# EPS_Distribution_RLCL-FPF.net
KiCad netlist of a schematic drawn in Altium Designer
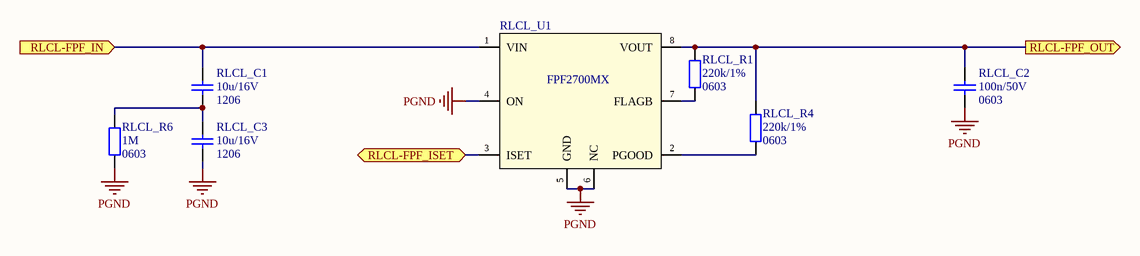
[diagram p0: EPS_Distribution_RLCL-FPF.SchDoc]

(export (version "E")
  (design (tool "Eeschema 10.0.6"))
  (components
    (comp (ref "RLCL_C1")
      (value "10u/16V")
      (footprint "SMD_Capacitor_1206")
      (description "Ceramic Cap Kemet COTS 10u/16V X7R 1206")
      (fields
        (field (name "MANUFACTURERPARTNUMBER") "C1206T106K4RACTU")
        (field (name "MANUFACTURER") "Kemet")
        (field (name "PACKGE") "1206")
      )
      (libsource (lib "capacitors") (part "Cer_C1206T106K4RACTU"))
    )
    (comp (ref "RLCL_C2")
      (value "100n/50V")
      (footprint "SMD_Capacitor_0603")
      (description "Ceramic Cap Kemet COTS 100n/50V X7R 0603")
      (fields
        (field (name "MANUFACTURER") "Kemet")
        (field (name "MANUFACTURERPARTNUMBER") "C0603T104K5RALTU")
        (field (name "PACKAGE") "0603")
      )
      (libsource (lib "capacitors") (part "Cer_C0603T104K5RALTU"))
    )
    (comp (ref "RLCL_C3")
      (value "10u/16V")
      (footprint "SMD_Capacitor_1206")
      (description "Ceramic Cap Kemet COTS 10u/16V X7R 1206")
      (fields
        (field (name "MANUFACTURERPARTNUMBER") "C1206T106K4RACTU")
        (field (name "MANUFACTURER") "Kemet")
        (field (name "PACKGE") "1206")
      )
      (libsource (lib "capacitors") (part "Cer_C1206T106K4RACTU"))
    )
    (comp (ref "RLCL_R1")
      (value "220k/1%")
      (footprint "SMD_Resistor_0603")
      (fields (field (name "PACKAGE") "0603"))
      (libsource (lib "resistors") (part "Res"))
    )
    (comp (ref "RLCL_R4")
      (value "220k/1%")
      (footprint "SMD_Resistor_0603")
      (fields (field (name "PACKAGE") "0603"))
      (libsource (lib "resistors") (part "Res"))
    )
    (comp (ref "RLCL_R6")
      (value "1M")
      (footprint "SMD_Resistor_0603")
      (fields (field (name "PACKAGE") "0603"))
      (libsource (lib "resistors") (part "Res"))
    )
    (comp (ref "RLCL_U1")
      (value "FPF2700MX")
      (footprint "SOIC-8-N")
      (description "Adj over-current protection 0.4-2A with auto-reset, Load Switch")
      (fields (field (name "MANUFACTURER") "Fairchild Semiconductor"))
      (libsource (lib "microcircuits") (part "FPF2700MX"))
    )
  )
  (nets
    (net (code "1") (name "/RLCL-FPF_IN") (class "Default")
      (node (ref "RLCL_C1") (pin "1") (pinfunction "1_1") (pintype "passive"))
      (node (ref "RLCL_U1") (pin "1") (pinfunction "VIN_1") (pintype "passive"))
    )
    (net (code "2") (name "/RLCL-FPF_ISET") (class "Default")
      (node (ref "RLCL_U1") (pin "3") (pinfunction "ISET_3") (pintype "passive"))
    )
    (net (code "3") (name "/RLCL-FPF_OUT") (class "Default")
      (node (ref "RLCL_C2") (pin "1") (pinfunction "1_1") (pintype "passive"))
      (node (ref "RLCL_R1") (pin "2") (pinfunction "2_2") (pintype "passive"))
      (node (ref "RLCL_R4") (pin "2") (pinfunction "2_2") (pintype "passive"))
      (node (ref "RLCL_U1") (pin "8") (pinfunction "VOUT_8") (pintype "passive"))
    )
    (net (code "4") (name "Net-(RLCL_C1-Pad2)") (class "Default")
      (node (ref "RLCL_C1") (pin "2") (pinfunction "2_2") (pintype "passive"))
      (node (ref "RLCL_C3") (pin "1") (pinfunction "1_1") (pintype "passive"))
      (node (ref "RLCL_R6") (pin "2") (pinfunction "2_2") (pintype "passive"))
    )
    (net (code "5") (name "Net-(RLCL_U1-FLAGB)") (class "Default")
      (node (ref "RLCL_R1") (pin "1") (pinfunction "1_1") (pintype "passive"))
      (node (ref "RLCL_U1") (pin "7") (pinfunction "FLAGB_7") (pintype "passive"))
    )
    (net (code "6") (name "Net-(RLCL_U1-PGOOD)") (class "Default")
      (node (ref "RLCL_R4") (pin "1") (pinfunction "1_1") (pintype "passive"))
      (node (ref "RLCL_U1") (pin "2") (pinfunction "PGOOD_2") (pintype "passive"))
    )
    (net (code "7") (name "PGND") (class "Default")
      (node (ref "RLCL_C2") (pin "2") (pinfunction "2_2") (pintype "passive"))
      (node (ref "RLCL_C3") (pin "2") (pinfunction "2_2") (pintype "passive"))
      (node (ref "RLCL_R6") (pin "1") (pinfunction "1_1") (pintype "passive"))
      (node (ref "RLCL_U1") (pin "4") (pinfunction "ON_4") (pintype "passive"))
      (node (ref "RLCL_U1") (pin "5") (pinfunction "GND_5") (pintype "passive"))
      (node (ref "RLCL_U1") (pin "6") (pinfunction "NC_6") (pintype "passive"))
    )
  )
)
